# camera.net
KiCad netlist of a schematic drawn in EAGLE
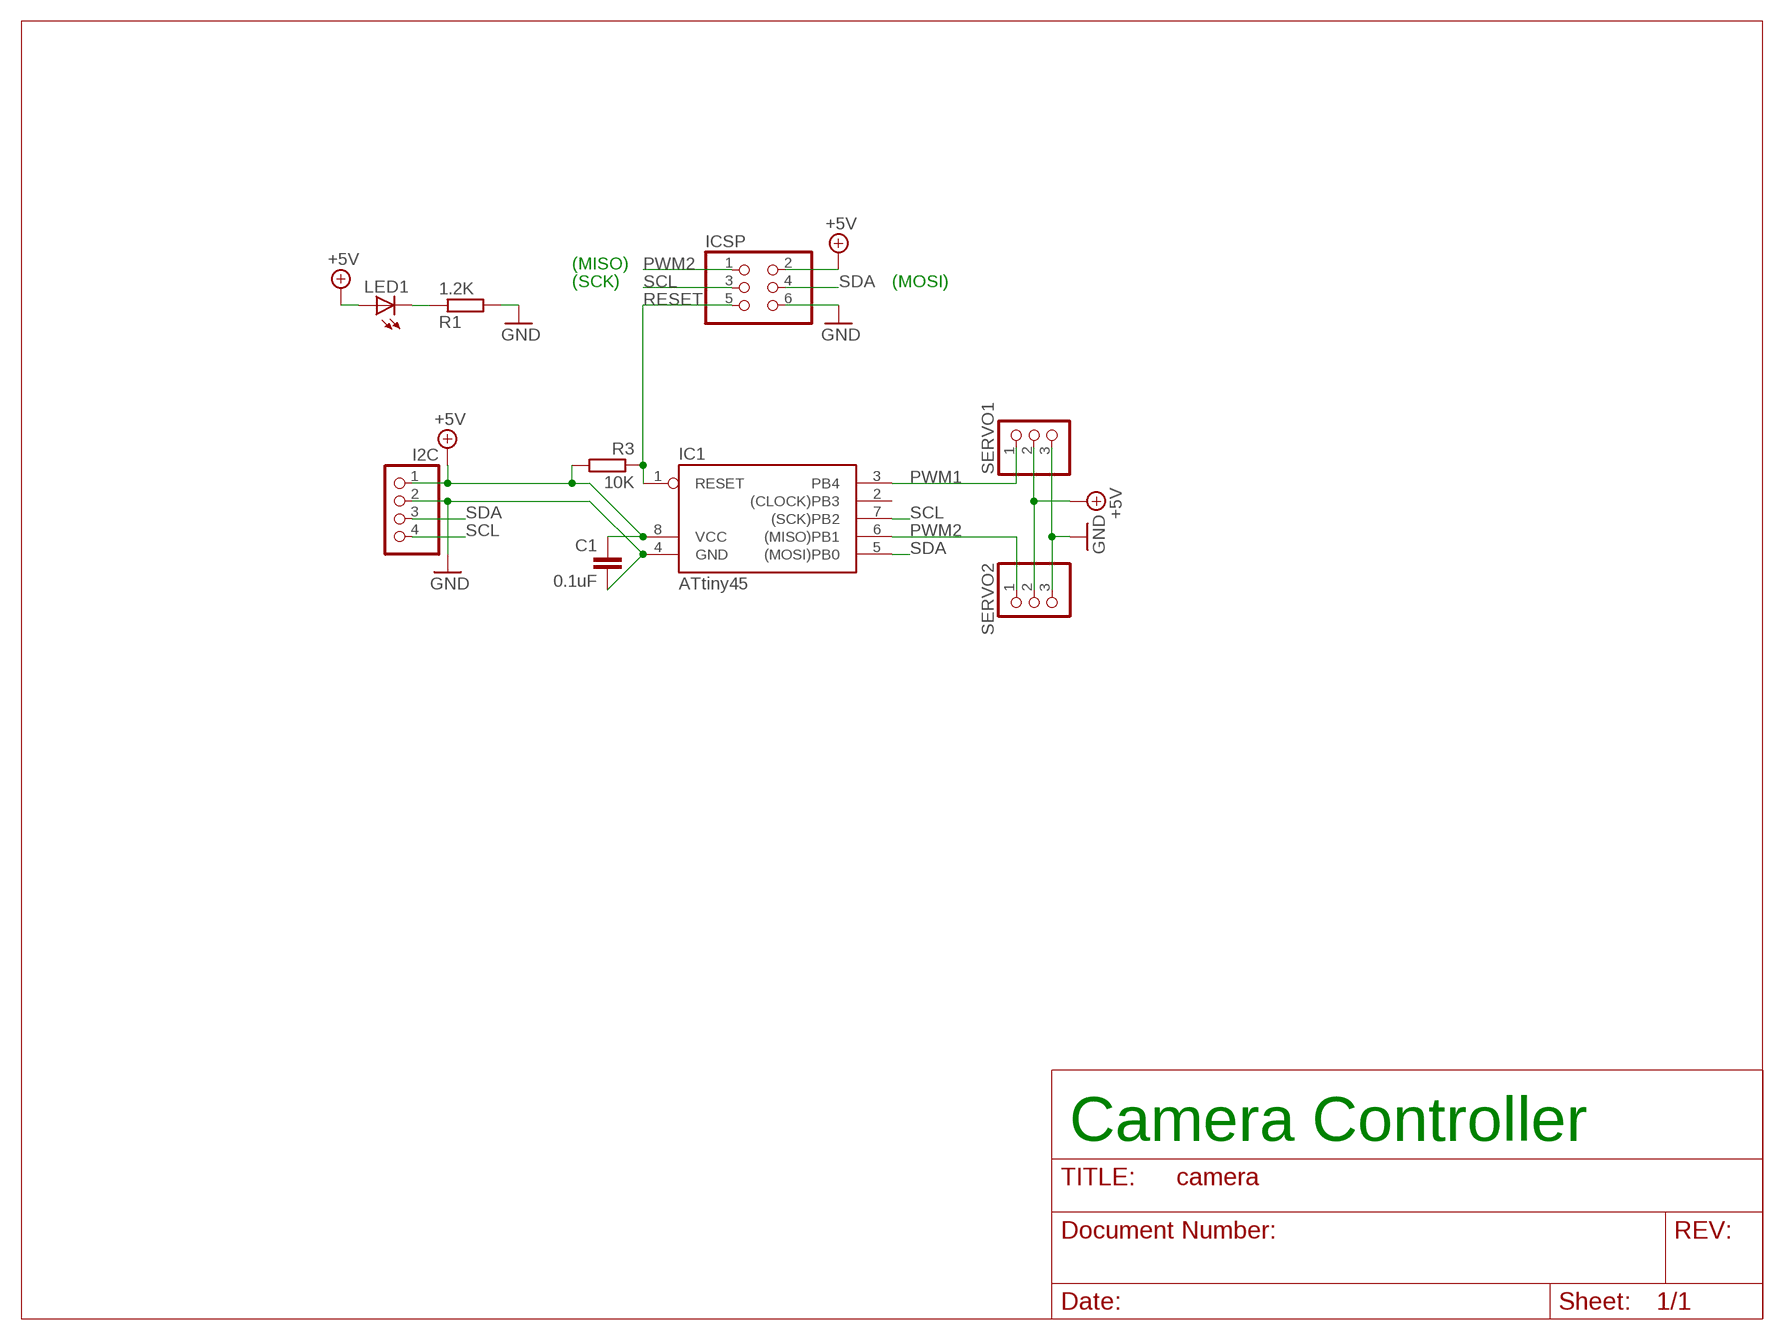
[diagram p0: schematic, sheet 1]

(export (version "E")
  (design (tool "Eeschema 10.0.6"))
  (components
    (comp (ref "C1")
      (value "0.1uF")
      (footprint "eagle-import:C025-024X044")
      (libsource (lib "eagle-import") (part "C-EU025-024X044"))
    )
    (comp (ref "I2C")
      (value "PINHD-1X4")
      (footprint "eagle-import:1X04")
      (libsource (lib "eagle-import") (part "PINHD-1X4"))
    )
    (comp (ref "IC1")
      (value "ATtiny45")
      (footprint "eagle-import:DIL08")
      (libsource (lib "eagle-import") (part "TINY22P"))
    )
    (comp (ref "ICSP")
      (value "PINHD-2X3")
      (footprint "eagle-import:2X03")
      (libsource (lib "eagle-import") (part "PINHD-2X3"))
    )
    (comp (ref "LED1")
      (value "LED5MM")
      (footprint "eagle-import:LED5MM")
      (libsource (lib "eagle-import") (part "LED5MM"))
    )
    (comp (ref "R1")
      (value "1.2K")
      (footprint "eagle-import:0207_2V")
      (libsource (lib "eagle-import") (part "R-EU_0207/2V"))
    )
    (comp (ref "R3")
      (value "10K")
      (footprint "eagle-import:0207_2V")
      (libsource (lib "eagle-import") (part "R-EU_0207/2V"))
    )
    (comp (ref "SERVO1")
      (value "PINHD-1X3")
      (footprint "eagle-import:1X03")
      (libsource (lib "eagle-import") (part "PINHD-1X3"))
    )
    (comp (ref "SERVO2")
      (value "PINHD-1X3")
      (footprint "eagle-import:1X03")
      (libsource (lib "eagle-import") (part "PINHD-1X3"))
    )
  )
  (nets
    (net (code "1") (name "+5V") (class "Default")
      (node (ref "C1") (pin "1") (pinfunction "1_1") (pintype "passive"))
      (node (ref "I2C") (pin "1") (pinfunction "1_1") (pintype "passive"))
      (node (ref "IC1") (pin "8") (pinfunction "VCC_8") (pintype "power_in"))
      (node (ref "ICSP") (pin "2") (pinfunction "2_2") (pintype "passive"))
      (node (ref "LED1") (pin "A") (pinfunction "A_A") (pintype "passive"))
      (node (ref "R3") (pin "2") (pinfunction "2_2") (pintype "passive"))
      (node (ref "SERVO1") (pin "2") (pinfunction "2_2") (pintype "passive"))
      (node (ref "SERVO2") (pin "2") (pinfunction "2_2") (pintype "passive"))
    )
    (net (code "2") (name "/PWM1") (class "Default")
      (node (ref "IC1") (pin "3") (pinfunction "PB4_3") (pintype "bidirectional"))
      (node (ref "SERVO1") (pin "1") (pinfunction "1_1") (pintype "passive"))
    )
    (net (code "3") (name "/PWM2") (class "Default")
      (node (ref "IC1") (pin "6") (pinfunction "(MISO)PB1_6") (pintype "bidirectional"))
      (node (ref "ICSP") (pin "1") (pinfunction "1_1") (pintype "passive"))
      (node (ref "SERVO2") (pin "1") (pinfunction "1_1") (pintype "passive"))
    )
    (net (code "4") (name "/RESET") (class "Default")
      (node (ref "IC1") (pin "1") (pinfunction "RESET_1") (pintype "input"))
      (node (ref "ICSP") (pin "5") (pinfunction "5_5") (pintype "passive"))
      (node (ref "R3") (pin "1") (pinfunction "1_1") (pintype "passive"))
    )
    (net (code "5") (name "/SCL") (class "Default")
      (node (ref "I2C") (pin "4") (pinfunction "4_4") (pintype "passive"))
      (node (ref "IC1") (pin "7") (pinfunction "(SCK)PB2_7") (pintype "bidirectional"))
      (node (ref "ICSP") (pin "3") (pinfunction "3_3") (pintype "passive"))
    )
    (net (code "6") (name "/SDA") (class "Default")
      (node (ref "I2C") (pin "3") (pinfunction "3_3") (pintype "passive"))
      (node (ref "IC1") (pin "5") (pinfunction "(MOSI)PB0_5") (pintype "bidirectional"))
      (node (ref "ICSP") (pin "4") (pinfunction "4_4") (pintype "passive"))
    )
    (net (code "7") (name "GND") (class "Default")
      (node (ref "C1") (pin "2") (pinfunction "2_2") (pintype "passive"))
      (node (ref "I2C") (pin "2") (pinfunction "2_2") (pintype "passive"))
      (node (ref "IC1") (pin "4") (pinfunction "GND_4") (pintype "power_in"))
      (node (ref "ICSP") (pin "6") (pinfunction "6_6") (pintype "passive"))
      (node (ref "R1") (pin "2") (pinfunction "2_2") (pintype "passive"))
      (node (ref "SERVO1") (pin "3") (pinfunction "3_3") (pintype "passive"))
      (node (ref "SERVO2") (pin "3") (pinfunction "3_3") (pintype "passive"))
    )
    (net (code "8") (name "Net-(LED1-C)") (class "Default")
      (node (ref "LED1") (pin "K") (pinfunction "C_K") (pintype "passive"))
      (node (ref "R1") (pin "1") (pinfunction "1_1") (pintype "passive"))
    )
    (net (code "9") (name "unconnected-(IC1-(CLOCK)PB3-Pad2)") (class "Default")
      (node (ref "IC1") (pin "2") (pinfunction "(CLOCK)PB3_2") (pintype "bidirectional"))
    )
  )
)
